# i2-mb_r2.net
KiCad netlist of a schematic drawn in EAGLE
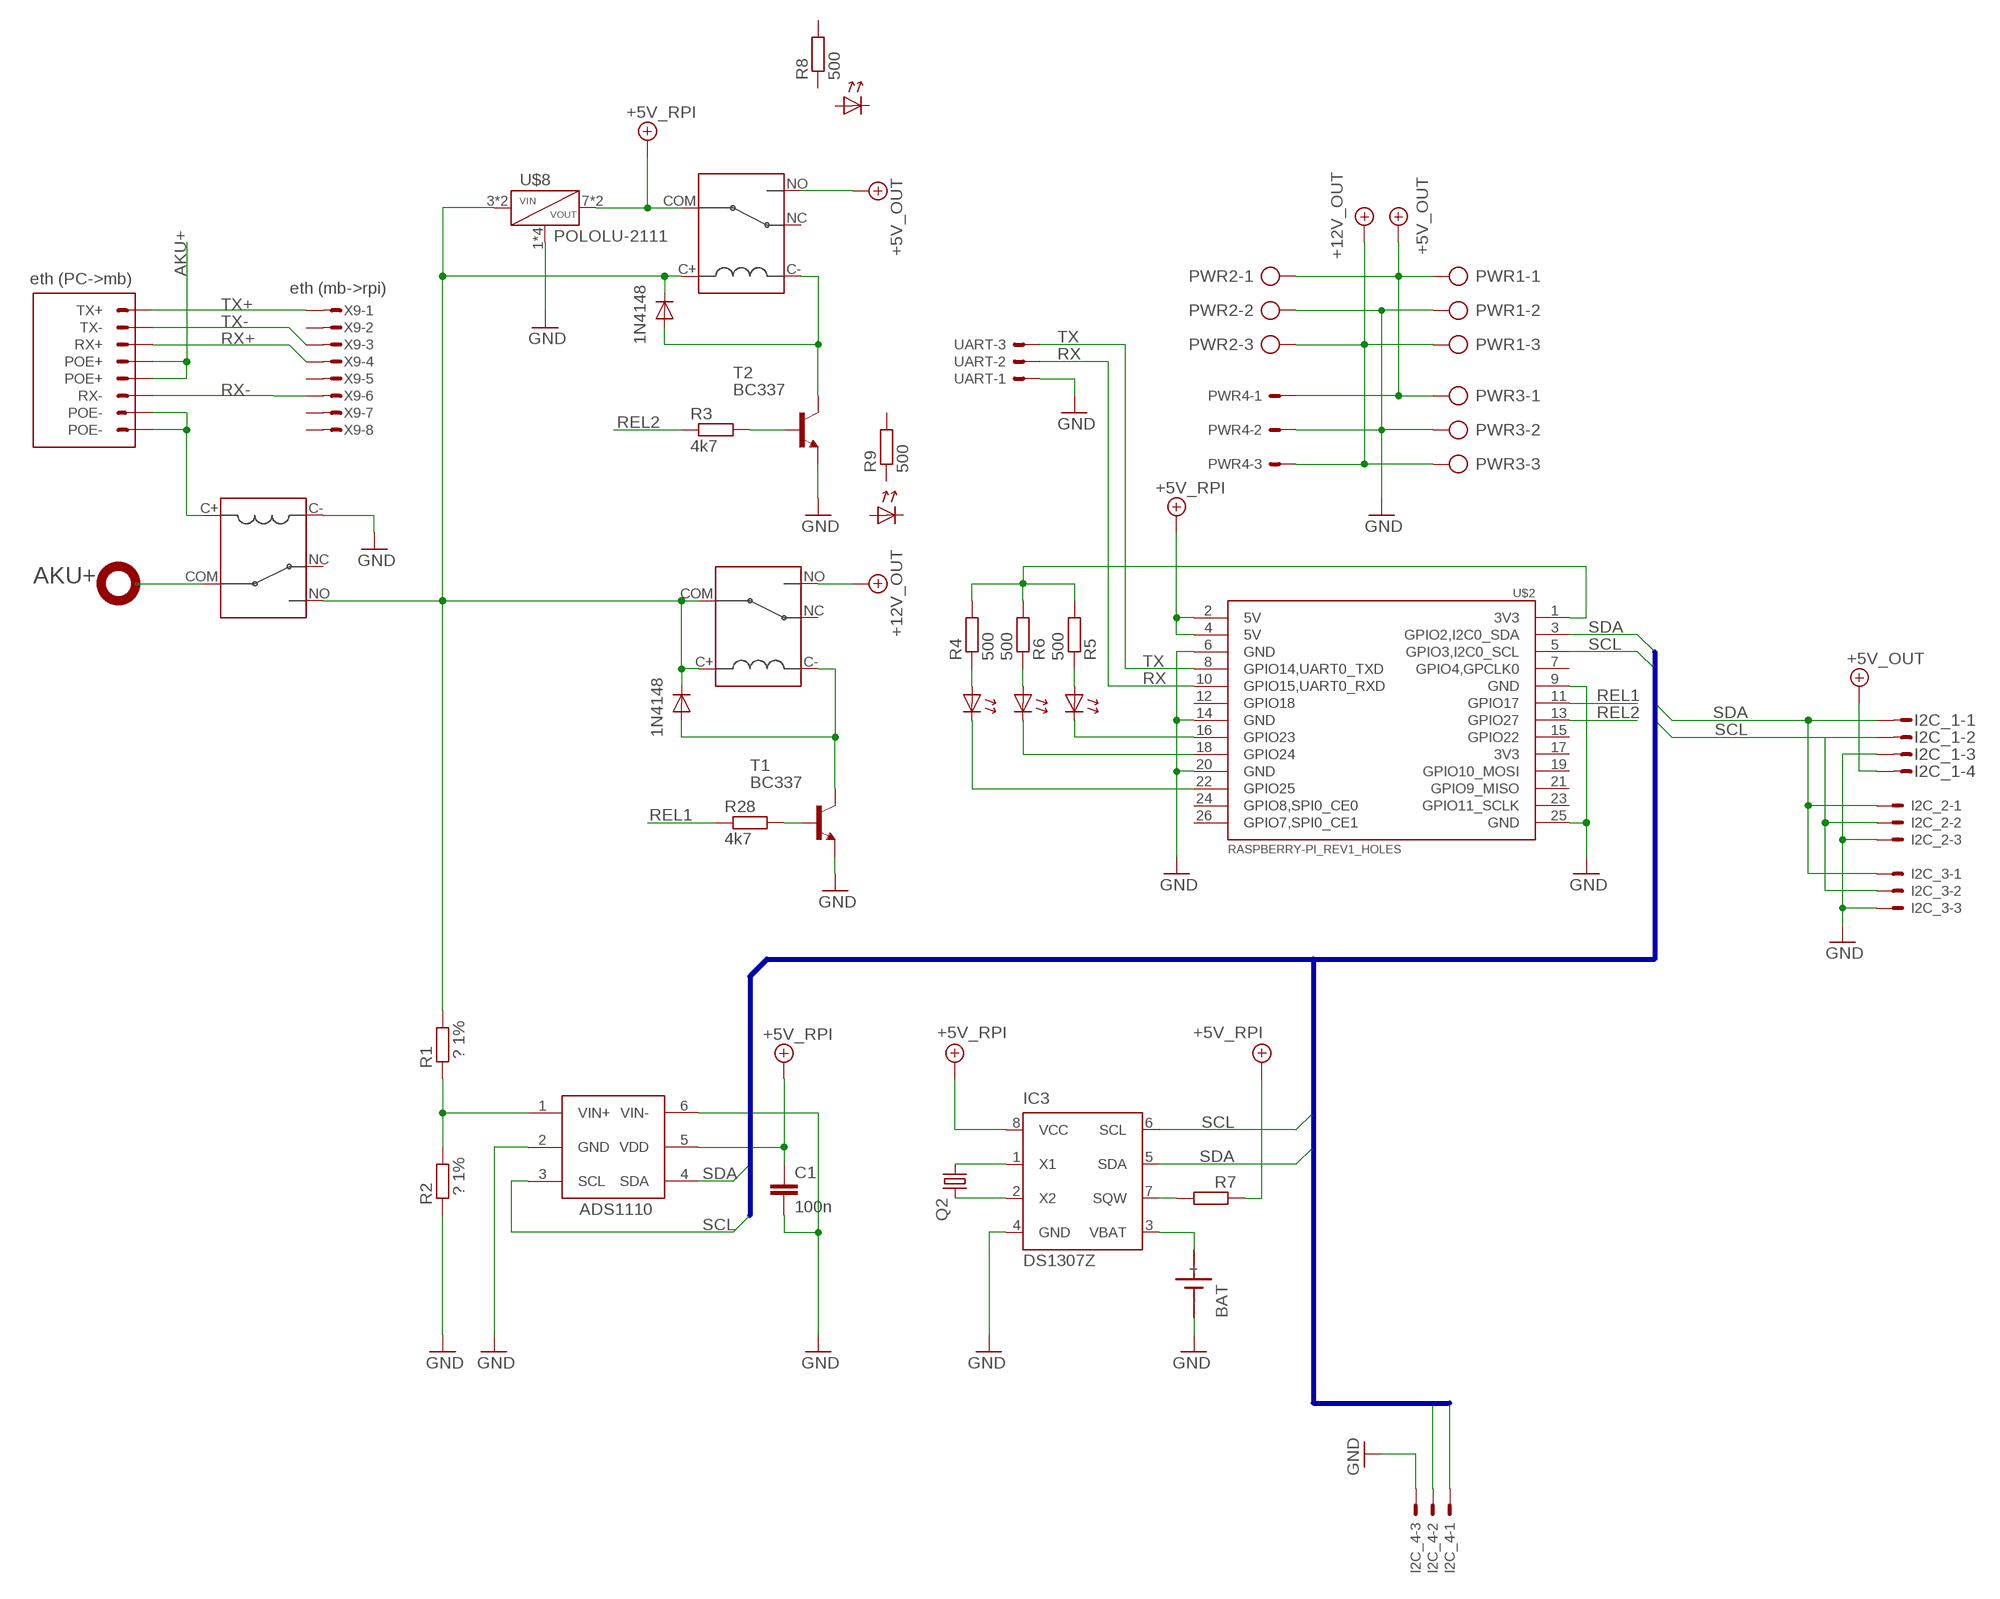
[diagram p0: schematic, sheet 1]

(export (version "E")
  (design (tool "Eeschema 10.0.6"))
  (components
    (comp (ref "BAT")
      (value "SN2032")
      (footprint "eagle-import:SN2032")
      (libsource (lib "eagle-import") (part "SN2032"))
    )
    (comp (ref "C1")
      (value "100n")
      (footprint "eagle-import:C0603")
      (libsource (lib "eagle-import") (part "C-EUC0603"))
    )
    (comp (ref "I2C_1")
      (value "MICROMATCH-4")
      (footprint "eagle-import:MICROMATCH-4")
      (fields (field (name "MPN") "7-215464-4"))
      (libsource (lib "eagle-import") (part "MICROMATCH-4"))
    )
    (comp (ref "I2C_2")
      (value "C-GRID-03-70553")
      (footprint "eagle-import:70553-03")
      (libsource (lib "eagle-import") (part "C-GRID-03-70553"))
    )
    (comp (ref "I2C_3")
      (value "C-GRID-03-70553")
      (footprint "eagle-import:70553-03")
      (libsource (lib "eagle-import") (part "C-GRID-03-70553"))
    )
    (comp (ref "I2C_4")
      (value "C-GRID-03-70553")
      (footprint "eagle-import:70553-03")
      (libsource (lib "eagle-import") (part "C-GRID-03-70553"))
    )
    (comp (ref "IC1")
      (value "ADS1110")
      (footprint "eagle-import:SOT-23-6")
      (libsource (lib "eagle-import") (part "ADS1110"))
    )
    (comp (ref "IC3")
      (value "DS1307Z")
      (footprint "eagle-import:SOIC8")
      (libsource (lib "eagle-import") (part "DS1307Z"))
    )
    (comp (ref "LED1")
      (value "LED0603")
      (footprint "eagle-import:D0603")
      (libsource (lib "eagle-import") (part "LED0603"))
    )
    (comp (ref "LED2")
      (value "LED0603")
      (footprint "eagle-import:D0603")
      (libsource (lib "eagle-import") (part "LED0603"))
    )
    (comp (ref "LED3")
      (value "LED0603")
      (footprint "eagle-import:D0603")
      (libsource (lib "eagle-import") (part "LED0603"))
    )
    (comp (ref "LED4")
      (value "LED0603")
      (footprint "eagle-import:D0603")
      (libsource (lib "eagle-import") (part "LED0603"))
    )
    (comp (ref "LED5")
      (value "LED0603")
      (footprint "eagle-import:D0603")
      (libsource (lib "eagle-import") (part "LED0603"))
    )
    (comp (ref "PWR1")
      (value "TBMP5103RC-KFV1")
      (footprint "eagle-import:TBMP5103RC-KF")
      (libsource (lib "eagle-import") (part "TBMP5103RC-KFV1"))
    )
    (comp (ref "PWR2")
      (value "TBMP5103RC-KFV1")
      (footprint "eagle-import:TBMP5103RC-KF")
      (libsource (lib "eagle-import") (part "TBMP5103RC-KFV1"))
    )
    (comp (ref "PWR3")
      (value "TBMP5103RC-KFV1")
      (footprint "eagle-import:TBMP5103RC-KF")
      (libsource (lib "eagle-import") (part "TBMP5103RC-KFV1"))
    )
    (comp (ref "PWR4")
      (value "C-GRID-03-70543")
      (footprint "eagle-import:70543-03")
      (libsource (lib "eagle-import") (part "C-GRID-03-70543"))
    )
    (comp (ref "Q2")
      (value "CRYSTAL")
      (footprint "eagle-import:CFPX-217")
      (libsource (lib "eagle-import") (part "CRYSTAL"))
    )
    (comp (ref "R1")
      (value "? 1%")
      (footprint "eagle-import:R0603")
      (libsource (lib "eagle-import") (part "R-EU_R0603"))
    )
    (comp (ref "R2")
      (value "? 1%")
      (footprint "eagle-import:R0603")
      (libsource (lib "eagle-import") (part "R-EU_R0603"))
    )
    (comp (ref "R3")
      (value "4k7")
      (footprint "eagle-import:R0603")
      (libsource (lib "eagle-import") (part "R-EU_R0603"))
    )
    (comp (ref "R4")
      (value "500")
      (footprint "eagle-import:R0603")
      (libsource (lib "eagle-import") (part "R-EU_R0603"))
    )
    (comp (ref "R5")
      (value "500")
      (footprint "eagle-import:R0603")
      (libsource (lib "eagle-import") (part "R-EU_R0603"))
    )
    (comp (ref "R6")
      (value "500")
      (footprint "eagle-import:R0603")
      (libsource (lib "eagle-import") (part "R-EU_R0603"))
    )
    (comp (ref "R7")
      (value "R-EU_R0603")
      (footprint "eagle-import:R0603")
      (libsource (lib "eagle-import") (part "R-EU_R0603"))
    )
    (comp (ref "R8")
      (value "500")
      (footprint "eagle-import:R0603")
      (libsource (lib "eagle-import") (part "R-EU_R0603"))
    )
    (comp (ref "R9")
      (value "500")
      (footprint "eagle-import:R0603")
      (libsource (lib "eagle-import") (part "R-EU_R0603"))
    )
    (comp (ref "R28")
      (value "4k7")
      (footprint "eagle-import:R0603")
      (libsource (lib "eagle-import") (part "R-EU_R0603"))
    )
    (comp (ref "T1")
      (value "BC337")
      (footprint "eagle-import:TO92")
      (libsource (lib "eagle-import") (part "BC337"))
    )
    (comp (ref "T2")
      (value "BC337")
      (footprint "eagle-import:TO92")
      (libsource (lib "eagle-import") (part "BC337"))
    )
    (comp (ref "U$2")
      (value "RASPBERRY-PI_REV1_HOLES")
      (footprint "eagle-import:RASPBERRY-PI_HOLES")
      (libsource (lib "eagle-import") (part "RASPBERRY-PI_REV1_HOLES"))
    )
    (comp (ref "U$3")
      (value "1N4148")
      (footprint "eagle-import:D0603")
      (libsource (lib "eagle-import") (part "D0603"))
    )
    (comp (ref "U$4")
      (value "1N4148")
      (footprint "eagle-import:D0603")
      (libsource (lib "eagle-import") (part "D0603"))
    )
    (comp (ref "U$5")
      (value "FBR51")
      (footprint "eagle-import:PC_RELAY")
      (libsource (lib "eagle-import") (part "FBR51"))
    )
    (comp (ref "U$6")
      (value "FBR51")
      (footprint "eagle-import:PC_RELAY")
      (libsource (lib "eagle-import") (part "FBR51"))
    )
    (comp (ref "U$7")
      (value "FBR51")
      (footprint "eagle-import:PC_RELAY")
      (libsource (lib "eagle-import") (part "FBR51"))
    )
    (comp (ref "U$8")
      (value "POLOLU-2111")
      (footprint "eagle-import:POLOLU-2111")
      (libsource (lib "eagle-import") (part "POLOLU-2111"))
    )
    (comp (ref "UART")
      (value "C-GRID-03-70543")
      (footprint "eagle-import:70543-03")
      (libsource (lib "eagle-import") (part "C-GRID-03-70543"))
    )
    (comp (ref "X9")
      (value "eth (mb->rpi)")
      (footprint "eagle-import:MICROMATCH-8")
      (libsource (lib "eagle-import") (part "MICROMATCH-8"))
    )
    (comp (ref "X_ETH")
      (value "eth (PC->mb)")
      (footprint "eagle-import:8P8C-TOP")
      (libsource (lib "eagle-import") (part "RJ45"))
    )
  )
  (nets
    (net (code "1") (name "+5V_OUT") (class "Default")
      (node (ref "I2C_1") (pin "4") (pinfunction "S_4") (pintype "passive"))
      (node (ref "PWR1") (pin "1") (pinfunction "P_1") (pintype "passive"))
      (node (ref "PWR2") (pin "1") (pinfunction "P_1") (pintype "passive"))
      (node (ref "PWR3") (pin "1") (pinfunction "P_1") (pintype "passive"))
      (node (ref "PWR4") (pin "1") (pinfunction "S_1") (pintype "passive"))
      (node (ref "U$5") (pin "NO") (pinfunction "NO_NO") (pintype "bidirectional"))
    )
    (net (code "2") (name "+5V_RPI") (class "Default")
      (node (ref "C1") (pin "1") (pinfunction "1_1") (pintype "passive"))
      (node (ref "IC1") (pin "5") (pinfunction "VDD_5") (pintype "bidirectional"))
      (node (ref "IC3") (pin "8") (pinfunction "VCC_8") (pintype "power_in"))
      (node (ref "R7") (pin "1") (pinfunction "1_1") (pintype "passive"))
      (node (ref "U$2") (pin "2") (pinfunction "5V_2") (pintype "bidirectional"))
      (node (ref "U$2") (pin "4") (pinfunction "5V_4") (pintype "bidirectional"))
      (node (ref "U$5") (pin "COM") (pinfunction "COM_COM") (pintype "bidirectional"))
      (node (ref "U$8") (pin "7") (pinfunction "VOUT_7") (pintype "passive"))
      (node (ref "U$8") (pin "8") (pinfunction "VOUT_8") (pintype "passive"))
    )
    (net (code "3") (name "+12V_OUT") (class "Default")
      (node (ref "PWR1") (pin "3") (pinfunction "P_3") (pintype "passive"))
      (node (ref "PWR2") (pin "3") (pinfunction "P_3") (pintype "passive"))
      (node (ref "PWR3") (pin "3") (pinfunction "P_3") (pintype "passive"))
      (node (ref "PWR4") (pin "3") (pinfunction "S_3") (pintype "passive"))
      (node (ref "U$7") (pin "NO") (pinfunction "NO_NO") (pintype "bidirectional"))
    )
    (net (code "4") (name "/AKU+") (class "Default")
      (node (ref "U$6") (pin "COM") (pinfunction "COM_COM") (pintype "bidirectional"))
      (node (ref "X_ETH") (pin "4") (pinfunction "POE+_4") (pintype "bidirectional"))
      (node (ref "X_ETH") (pin "5") (pinfunction "POE+_5") (pintype "bidirectional"))
    )
    (net (code "5") (name "/REL1") (class "Default")
      (node (ref "R28") (pin "1") (pinfunction "1_1") (pintype "passive"))
      (node (ref "U$2") (pin "11") (pinfunction "GPIO17_11") (pintype "bidirectional"))
    )
    (net (code "6") (name "/REL2") (class "Default")
      (node (ref "R3") (pin "1") (pinfunction "1_1") (pintype "passive"))
      (node (ref "U$2") (pin "13") (pinfunction "GPIO27_13") (pintype "bidirectional"))
    )
    (net (code "7") (name "/RX") (class "Default")
      (node (ref "U$2") (pin "10") (pinfunction "GPIO15,UART0_RXD_10") (pintype "bidirectional"))
      (node (ref "UART") (pin "2") (pinfunction "S_2") (pintype "passive"))
    )
    (net (code "8") (name "/RX+") (class "Default")
      (node (ref "X9") (pin "4") (pinfunction "S_4") (pintype "passive"))
      (node (ref "X_ETH") (pin "3") (pinfunction "RX+_3") (pintype "bidirectional"))
    )
    (net (code "9") (name "/RX-") (class "Default")
      (node (ref "X9") (pin "6") (pinfunction "S_6") (pintype "passive"))
      (node (ref "X_ETH") (pin "6") (pinfunction "RX-_6") (pintype "bidirectional"))
    )
    (net (code "10") (name "/SCL") (class "Default")
      (node (ref "I2C_1") (pin "2") (pinfunction "S_2") (pintype "passive"))
      (node (ref "I2C_2") (pin "2") (pinfunction "S_2") (pintype "passive"))
      (node (ref "I2C_3") (pin "2") (pinfunction "S_2") (pintype "passive"))
      (node (ref "I2C_4") (pin "2") (pinfunction "S_2") (pintype "passive"))
      (node (ref "IC1") (pin "3") (pinfunction "SCL_3") (pintype "bidirectional"))
      (node (ref "IC3") (pin "6") (pinfunction "SCL_6") (pintype "input"))
      (node (ref "U$2") (pin "5") (pinfunction "GPIO3,I2C0_SCL_5") (pintype "bidirectional"))
    )
    (net (code "11") (name "/SDA") (class "Default")
      (node (ref "I2C_1") (pin "1") (pinfunction "S_1") (pintype "passive"))
      (node (ref "I2C_2") (pin "1") (pinfunction "S_1") (pintype "passive"))
      (node (ref "I2C_3") (pin "1") (pinfunction "S_1") (pintype "passive"))
      (node (ref "I2C_4") (pin "1") (pinfunction "S_1") (pintype "passive"))
      (node (ref "IC1") (pin "4") (pinfunction "SDA_4") (pintype "bidirectional"))
      (node (ref "IC3") (pin "5") (pinfunction "SDA_5") (pintype "bidirectional"))
      (node (ref "U$2") (pin "3") (pinfunction "GPIO2,I2C0_SDA_3") (pintype "bidirectional"))
    )
    (net (code "12") (name "/TX") (class "Default")
      (node (ref "U$2") (pin "8") (pinfunction "GPIO14,UART0_TXD_8") (pintype "bidirectional"))
      (node (ref "UART") (pin "3") (pinfunction "S_3") (pintype "passive"))
    )
    (net (code "13") (name "/TX+") (class "Default")
      (node (ref "X9") (pin "1") (pinfunction "S_1") (pintype "passive"))
      (node (ref "X_ETH") (pin "1") (pinfunction "TX+_1") (pintype "bidirectional"))
    )
    (net (code "14") (name "/TX-") (class "Default")
      (node (ref "X9") (pin "3") (pinfunction "S_3") (pintype "passive"))
      (node (ref "X_ETH") (pin "2") (pinfunction "TX-_2") (pintype "bidirectional"))
    )
    (net (code "15") (name "GND") (class "Default")
      (node (ref "BAT") (pin "-") (pinfunction "-_-") (pintype "passive"))
      (node (ref "C1") (pin "2") (pinfunction "2_2") (pintype "passive"))
      (node (ref "I2C_1") (pin "3") (pinfunction "S_3") (pintype "passive"))
      (node (ref "I2C_2") (pin "3") (pinfunction "S_3") (pintype "passive"))
      (node (ref "I2C_3") (pin "3") (pinfunction "S_3") (pintype "passive"))
      (node (ref "I2C_4") (pin "3") (pinfunction "S_3") (pintype "passive"))
      (node (ref "IC1") (pin "2") (pinfunction "GND_2") (pintype "bidirectional"))
      (node (ref "IC1") (pin "6") (pinfunction "VIN-_6") (pintype "bidirectional"))
      (node (ref "IC3") (pin "4") (pinfunction "GND_4") (pintype "power_in"))
      (node (ref "PWR1") (pin "2") (pinfunction "P_2") (pintype "passive"))
      (node (ref "PWR2") (pin "2") (pinfunction "P_2") (pintype "passive"))
      (node (ref "PWR3") (pin "2") (pinfunction "P_2") (pintype "passive"))
      (node (ref "PWR4") (pin "2") (pinfunction "S_2") (pintype "passive"))
      (node (ref "R2") (pin "2") (pinfunction "2_2") (pintype "passive"))
      (node (ref "T1") (pin "1") (pinfunction "E_1") (pintype "passive"))
      (node (ref "T2") (pin "1") (pinfunction "E_1") (pintype "passive"))
      (node (ref "U$2") (pin "14") (pinfunction "GND_14") (pintype "bidirectional"))
      (node (ref "U$2") (pin "20") (pinfunction "GND_20") (pintype "bidirectional"))
      (node (ref "U$2") (pin "25") (pinfunction "GND_25") (pintype "bidirectional"))
      (node (ref "U$2") (pin "6") (pinfunction "GND_6") (pintype "bidirectional"))
      (node (ref "U$2") (pin "9") (pinfunction "GND_9") (pintype "bidirectional"))
      (node (ref "U$6") (pin "C-") (pinfunction "C-_C-") (pintype "bidirectional"))
      (node (ref "U$8") (pin "1") (pinfunction "GND_1") (pintype "passive"))
      (node (ref "U$8") (pin "2") (pinfunction "GND_2") (pintype "passive"))
      (node (ref "U$8") (pin "5") (pinfunction "GND_5") (pintype "passive"))
      (node (ref "U$8") (pin "6") (pinfunction "GND_6") (pintype "passive"))
      (node (ref "UART") (pin "1") (pinfunction "S_1") (pintype "passive"))
    )
    (net (code "16") (name "Net-(IC1-VIN+)") (class "Default")
      (node (ref "IC1") (pin "1") (pinfunction "VIN+_1") (pintype "bidirectional"))
      (node (ref "R1") (pin "2") (pinfunction "2_2") (pintype "passive"))
      (node (ref "R2") (pin "1") (pinfunction "1_1") (pintype "passive"))
    )
    (net (code "17") (name "Net-(IC3-SQW)") (class "Default")
      (node (ref "IC3") (pin "7") (pinfunction "SQW_7") (pintype "open_collector"))
      (node (ref "R7") (pin "2") (pinfunction "2_2") (pintype "passive"))
    )
    (net (code "18") (name "Net-(IC3-VBAT)") (class "Default")
      (node (ref "BAT") (pin "+") (pinfunction "+_+") (pintype "passive"))
      (node (ref "IC3") (pin "3") (pinfunction "VBAT_3") (pintype "passive"))
    )
    (net (code "19") (name "Net-(IC3-X1)") (class "Default")
      (node (ref "IC3") (pin "1") (pinfunction "X1_1") (pintype "input"))
      (node (ref "Q2") (pin "1") (pinfunction "1_1") (pintype "passive"))
    )
    (net (code "20") (name "Net-(IC3-X2)") (class "Default")
      (node (ref "IC3") (pin "2") (pinfunction "X2_2") (pintype "output"))
      (node (ref "Q2") (pin "2") (pinfunction "2_2") (pintype "passive"))
    )
    (net (code "21") (name "Net-(LED1-A)") (class "Default")
      (node (ref "LED1") (pin "1") (pinfunction "A_1") (pintype "passive"))
      (node (ref "R4") (pin "1") (pinfunction "1_1") (pintype "passive"))
    )
    (net (code "22") (name "Net-(LED1-C)") (class "Default")
      (node (ref "LED1") (pin "2") (pinfunction "C_2") (pintype "passive"))
      (node (ref "U$2") (pin "22") (pinfunction "GPIO25_22") (pintype "bidirectional"))
    )
    (net (code "23") (name "Net-(LED2-A)") (class "Default")
      (node (ref "LED2") (pin "1") (pinfunction "A_1") (pintype "passive"))
      (node (ref "R5") (pin "1") (pinfunction "1_1") (pintype "passive"))
    )
    (net (code "24") (name "Net-(LED2-C)") (class "Default")
      (node (ref "LED2") (pin "2") (pinfunction "C_2") (pintype "passive"))
      (node (ref "U$2") (pin "16") (pinfunction "GPIO23_16") (pintype "bidirectional"))
    )
    (net (code "25") (name "Net-(LED3-A)") (class "Default")
      (node (ref "LED3") (pin "1") (pinfunction "A_1") (pintype "passive"))
      (node (ref "R6") (pin "1") (pinfunction "1_1") (pintype "passive"))
    )
    (net (code "26") (name "Net-(LED3-C)") (class "Default")
      (node (ref "LED3") (pin "2") (pinfunction "C_2") (pintype "passive"))
      (node (ref "U$2") (pin "18") (pinfunction "GPIO24_18") (pintype "bidirectional"))
    )
    (net (code "27") (name "Net-(R4-Pad2)") (class "Default")
      (node (ref "R4") (pin "2") (pinfunction "2_2") (pintype "passive"))
      (node (ref "R5") (pin "2") (pinfunction "2_2") (pintype "passive"))
      (node (ref "R6") (pin "2") (pinfunction "2_2") (pintype "passive"))
      (node (ref "U$2") (pin "1") (pinfunction "3V3_1") (pintype "bidirectional"))
    )
    (net (code "28") (name "Net-(T1-B)") (class "Default")
      (node (ref "R28") (pin "2") (pinfunction "2_2") (pintype "passive"))
      (node (ref "T1") (pin "2") (pinfunction "B_2") (pintype "passive"))
    )
    (net (code "29") (name "Net-(T1-C)") (class "Default")
      (node (ref "T1") (pin "3") (pinfunction "C_3") (pintype "passive"))
      (node (ref "U$4") (pin "1") (pinfunction "A_1") (pintype "passive"))
      (node (ref "U$7") (pin "C-") (pinfunction "C-_C-") (pintype "bidirectional"))
    )
    (net (code "30") (name "Net-(T2-B)") (class "Default")
      (node (ref "R3") (pin "2") (pinfunction "2_2") (pintype "passive"))
      (node (ref "T2") (pin "2") (pinfunction "B_2") (pintype "passive"))
    )
    (net (code "31") (name "Net-(T2-C)") (class "Default")
      (node (ref "T2") (pin "3") (pinfunction "C_3") (pintype "passive"))
      (node (ref "U$3") (pin "1") (pinfunction "A_1") (pintype "passive"))
      (node (ref "U$5") (pin "C-") (pinfunction "C-_C-") (pintype "bidirectional"))
    )
    (net (code "32") (name "Net-(U$3-C)") (class "Default")
      (node (ref "R1") (pin "1") (pinfunction "1_1") (pintype "passive"))
      (node (ref "U$3") (pin "2") (pinfunction "C_2") (pintype "passive"))
      (node (ref "U$4") (pin "2") (pinfunction "C_2") (pintype "passive"))
      (node (ref "U$5") (pin "C+") (pinfunction "C+_C+") (pintype "bidirectional"))
      (node (ref "U$6") (pin "NO") (pinfunction "NO_NO") (pintype "bidirectional"))
      (node (ref "U$7") (pin "C+") (pinfunction "C+_C+") (pintype "bidirectional"))
      (node (ref "U$7") (pin "COM") (pinfunction "COM_COM") (pintype "bidirectional"))
      (node (ref "U$8") (pin "3") (pinfunction "VIN_3") (pintype "passive"))
      (node (ref "U$8") (pin "4") (pinfunction "VIN_4") (pintype "passive"))
    )
    (net (code "33") (name "Net-(U$6-PadC+)") (class "Default")
      (node (ref "U$6") (pin "C+") (pinfunction "C+_C+") (pintype "bidirectional"))
      (node (ref "X_ETH") (pin "7") (pinfunction "POE-_7") (pintype "bidirectional"))
      (node (ref "X_ETH") (pin "8") (pinfunction "POE-_8") (pintype "bidirectional"))
    )
    (net (code "34") (name "unconnected-(LED4-A-Pad1)") (class "Default")
      (node (ref "LED4") (pin "1") (pinfunction "A_1") (pintype "passive"))
    )
    (net (code "35") (name "unconnected-(LED4-C-Pad2)") (class "Default")
      (node (ref "LED4") (pin "2") (pinfunction "C_2") (pintype "passive"))
    )
    (net (code "36") (name "unconnected-(LED5-A-Pad1)") (class "Default")
      (node (ref "LED5") (pin "1") (pinfunction "A_1") (pintype "passive"))
    )
    (net (code "37") (name "unconnected-(LED5-C-Pad2)") (class "Default")
      (node (ref "LED5") (pin "2") (pinfunction "C_2") (pintype "passive"))
    )
    (net (code "38") (name "unconnected-(R8-Pad1)") (class "Default")
      (node (ref "R8") (pin "1") (pinfunction "1_1") (pintype "passive"))
    )
    (net (code "39") (name "unconnected-(R8-Pad2)") (class "Default")
      (node (ref "R8") (pin "2") (pinfunction "2_2") (pintype "passive"))
    )
    (net (code "40") (name "unconnected-(R9-Pad1)") (class "Default")
      (node (ref "R9") (pin "1") (pinfunction "1_1") (pintype "passive"))
    )
    (net (code "41") (name "unconnected-(R9-Pad2)") (class "Default")
      (node (ref "R9") (pin "2") (pinfunction "2_2") (pintype "passive"))
    )
    (net (code "42") (name "unconnected-(U$2-3V3-Pad17)") (class "Default")
      (node (ref "U$2") (pin "17") (pinfunction "3V3_17") (pintype "bidirectional"))
    )
    (net (code "43") (name "unconnected-(U$2-GPIO4,GPCLK0-Pad7)") (class "Default")
      (node (ref "U$2") (pin "7") (pinfunction "GPIO4,GPCLK0_7") (pintype "bidirectional"))
    )
    (net (code "44") (name "unconnected-(U$2-GPIO7,SPI0_CE1-Pad26)") (class "Default")
      (node (ref "U$2") (pin "26") (pinfunction "GPIO7,SPI0_CE1_26") (pintype "bidirectional"))
    )
    (net (code "45") (name "unconnected-(U$2-GPIO8,SPI0_CE0-Pad24)") (class "Default")
      (node (ref "U$2") (pin "24") (pinfunction "GPIO8,SPI0_CE0_24") (pintype "bidirectional"))
    )
    (net (code "46") (name "unconnected-(U$2-GPIO9_MISO-Pad21)") (class "Default")
      (node (ref "U$2") (pin "21") (pinfunction "GPIO9_MISO_21") (pintype "bidirectional"))
    )
    (net (code "47") (name "unconnected-(U$2-GPIO10_MOSI-Pad19)") (class "Default")
      (node (ref "U$2") (pin "19") (pinfunction "GPIO10_MOSI_19") (pintype "bidirectional"))
    )
    (net (code "48") (name "unconnected-(U$2-GPIO11_SCLK-Pad23)") (class "Default")
      (node (ref "U$2") (pin "23") (pinfunction "GPIO11_SCLK_23") (pintype "bidirectional"))
    )
    (net (code "49") (name "unconnected-(U$2-GPIO18-Pad12)") (class "Default")
      (node (ref "U$2") (pin "12") (pinfunction "GPIO18_12") (pintype "bidirectional"))
    )
    (net (code "50") (name "unconnected-(U$2-GPIO22-Pad15)") (class "Default")
      (node (ref "U$2") (pin "15") (pinfunction "GPIO22_15") (pintype "bidirectional"))
    )
    (net (code "51") (name "unconnected-(U$5-PadNC)") (class "Default")
      (node (ref "U$5") (pin "NC") (pinfunction "NC_NC") (pintype "bidirectional"))
    )
    (net (code "52") (name "unconnected-(U$6-PadNC)") (class "Default")
      (node (ref "U$6") (pin "NC") (pinfunction "NC_NC") (pintype "bidirectional"))
    )
    (net (code "53") (name "unconnected-(U$7-PadNC)") (class "Default")
      (node (ref "U$7") (pin "NC") (pinfunction "NC_NC") (pintype "bidirectional"))
    )
    (net (code "54") (name "unconnected-(X9B-S-Pad2)") (class "Default")
      (node (ref "X9") (pin "2") (pinfunction "S_2") (pintype "passive"))
    )
    (net (code "55") (name "unconnected-(X9E-S-Pad5)") (class "Default")
      (node (ref "X9") (pin "5") (pinfunction "S_5") (pintype "passive"))
    )
    (net (code "56") (name "unconnected-(X9G-S-Pad7)") (class "Default")
      (node (ref "X9") (pin "7") (pinfunction "S_7") (pintype "passive"))
    )
    (net (code "57") (name "unconnected-(X9H-S-Pad8)") (class "Default")
      (node (ref "X9") (pin "8") (pinfunction "S_8") (pintype "passive"))
    )
  )
)
